# 04-POWER-P12V.net
KiCad netlist of a schematic drawn in Altium Designer
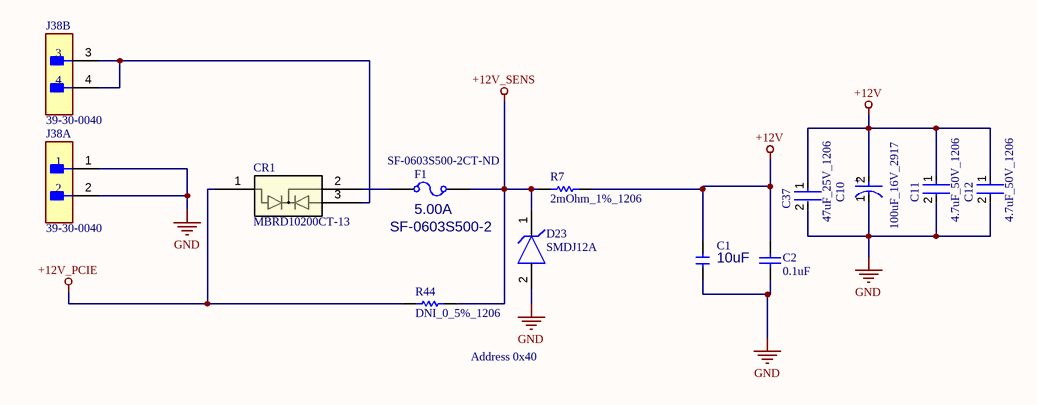
[diagram p0: 04-POWER-P12V.SchDoc]

(export (version "E")
  (design (tool "Eeschema 10.0.6"))
  (components
    (comp (ref "C1")
      (value "10uF")
      (footprint "CAPC2012X14N")
      (description "CAP, CER, 10.UF, 25V, 10%, X5R, 0805")
      (fields
        (field (name "MFG PART NUM") "TMK212BBJ106KG-T")
        (field (name "VALENTIUM PART NUM") "<VALENTIUM>")
      )
      (libsource (lib "Capacitors") (part "CAP_0805_10UF_25V"))
    )
    (comp (ref "C2")
      (value "0.1uF")
      (footprint "CAPC1608X87X45ML20T05")
      (description "C0603X104K5RACAUTO")
      (fields (field (name "MANUFACTURER") "Kemet"))
      (libsource (lib "Altium Content Vault") (part "CAP"))
    )
    (comp (ref "C10")
      (value "100uF_16V_2917")
      (footprint "FP-T495D107K016ATE125-MFG")
      (description "CAP TANT 100UF 10% 16V 2917")
      (fields (field (name "VOLTAGE") "16V") (field (name "TOLERANCE") "10%"))
      (libsource (lib "Altium Content Vault") (part "a00bbbee19879c290e62620ae7e47b1"))
    )
    (comp (ref "C11")
      (value "4.7uF_50V_1206")
      (footprint "FP-GRM31C-0_2-e0_3_0_8-IPC_C")
      (description "Chip Multilayer Ceramic Capacitors for General Purpose, 1206, 4.7uF, X7R, 15%, 10%, 50V")
      (fields (field (name "VOLTAGE") "50V") (field (name "TOLERANCE") "10%"))
      (libsource (lib "Altium Content Vault") (part "02cd4be3c70576c341d710602a673aa"))
    )
    (comp (ref "C12")
      (value "4.7uF_50V_1206")
      (footprint "FP-GRM31C-0_2-e0_3_0_8-IPC_C")
      (description "Chip Multilayer Ceramic Capacitors for General Purpose, 1206, 4.7uF, X7R, 15%, 10%, 50V")
      (fields (field (name "VOLTAGE") "50V") (field (name "TOLERANCE") "10%"))
      (libsource (lib "Altium Content Vault") (part "02cd4be3c70576c341d710602a673aa"))
    )
    (comp (ref "C37")
      (value "47uF_25V_1206")
      (footprint "FP-C3216-160-0_2-MFG")
      (description "Multilayer Ceramic Capacitors 47uF ±20% 25V X5R SMD 1206")
      (fields (field (name "VOLTAGE") "25V") (field (name "TOLERANCE") "20%"))
      (libsource (lib "Altium Content Vault") (part "11868f565c42a9108669ba33697ecf6"))
    )
    (comp (ref "CR1")
      (value "MBRD10200CT-13")
      (footprint "TO252(DPAK)_DIO")
      (description "No Description Available")
      (libsource (lib "MBRD10200CT-13") (part "MBRD10200CT-13"))
    )
    (comp (ref "D23")
      (value "SMDJ12A")
      (footprint "FP-DO-214AB_SMC_J-Bend-MFG")
      (description "TVS DIODE 12V 19.9V DO214AB")
      (libsource (lib "Altium Content Vault") (part "673ecd2ea4d7fb87b4005b0cb348b7d"))
    )
    (comp (ref "F1")
      (value "5.00A")
      (footprint "FUSM1608X60N")
      (description "FUSE SLOW 5.00A 32V M 0603")
      (fields
        (field (name "MFG PART NUM") "SF-0603S500-2")
        (field (name "VALENTIUM PART NUM") "<VALENTIUM>")
        (field (name "SUPPLIER PART NUMBER 1") "SF-0603S500-2CT-ND")
        (field (name "Comment") "FUSE_0603_5.00A")
      )
      (libsource (lib "Passives") (part "FUSE_0603_2.00A"))
    )
    (comp (ref "J38")
      (value "39-30-0040")
      (footprint "FP-39-30-0040-MFG")
      (description "CONN HEADER R/A 4POS 4.2MM")
      (fields
        (field (name "OCTOPART") "https://octopart.com/39-30-0040-molex-277428")
        (field (name "MANUFACTURER") "Molex")
      )
      (libsource (lib "Altium Content Vault") (part "ac72c5313ea981db199dbd0e8237b04"))
    )
    (comp (ref "R7")
      (value "2mOhm_1%_1206")
      (footprint "RESC3216X89X64NL25T25")
      (fields (field (name "MANUFACTURER") "Vishay Dale") (field (name "PART NUMBER") "WSL12062L000FEA18"))
      (libsource (lib "Altium Content Vault") (part "RES"))
    )
    (comp (ref "R44")
      (value "DNI_0_5%_1206")
      (footprint "RESC3116X65X50ML20T20")
      (fields (field (name "PART NUMBER") "CRCW12060000Z0EAHP") (field (name "MANUFACTURER") "Vishay Dale"))
      (libsource (lib "Altium Content Vault") (part "RES"))
    )
  )
  (nets
    (net (code "1") (name "+12V") (class "Default")
      (node (ref "C1") (pin "1") (pinfunction "1_1") (pintype "passive"))
      (node (ref "C10") (pin "2") (pinfunction "A_2") (pintype "passive"))
      (node (ref "C11") (pin "1") (pinfunction "1_1") (pintype "passive"))
      (node (ref "C12") (pin "1") (pinfunction "1_1") (pintype "passive"))
      (node (ref "C2") (pin "2") (pinfunction "2_2") (pintype "passive"))
      (node (ref "C37") (pin "1") (pinfunction "1_1") (pintype "passive"))
      (node (ref "R7") (pin "2") (pinfunction "2_2") (pintype "passive"))
    )
    (net (code "2") (name "+12V_PCIE") (class "Default")
      (node (ref "CR1") (pin "1") (pinfunction "1_1") (pintype "passive"))
      (node (ref "R44") (pin "1") (pinfunction "1_1") (pintype "passive"))
    )
    (net (code "3") (name "+12V_SENS") (class "Default")
      (node (ref "D23") (pin "1") (pinfunction "C_1") (pintype "passive"))
      (node (ref "F1") (pin "2") (pinfunction "2_2") (pintype "passive"))
      (node (ref "R44") (pin "2") (pinfunction "2_2") (pintype "passive"))
      (node (ref "R7") (pin "1") (pinfunction "1_1") (pintype "passive"))
    )
    (net (code "4") (name "GND") (class "Default")
      (node (ref "C1") (pin "2") (pinfunction "2_2") (pintype "passive"))
      (node (ref "C10") (pin "1") (pinfunction "C_1") (pintype "passive"))
      (node (ref "C11") (pin "2") (pinfunction "2_2") (pintype "passive"))
      (node (ref "C12") (pin "2") (pinfunction "2_2") (pintype "passive"))
      (node (ref "C2") (pin "1") (pinfunction "1_1") (pintype "passive"))
      (node (ref "C37") (pin "2") (pinfunction "2_2") (pintype "passive"))
      (node (ref "D23") (pin "2") (pinfunction "A_2") (pintype "passive"))
      (node (ref "J38") (pin "1") (pinfunction "1_1") (pintype "passive"))
      (node (ref "J38") (pin "2") (pinfunction "2_2") (pintype "passive"))
    )
    (net (code "5") (name "Net-(CR1-Pad2)") (class "Default")
      (node (ref "CR1") (pin "2") (pinfunction "2_2") (pintype "passive"))
      (node (ref "F1") (pin "1") (pinfunction "1_1") (pintype "passive"))
    )
    (net (code "6") (name "Net-(CR1-Pad3)") (class "Default")
      (node (ref "CR1") (pin "3") (pinfunction "3_3") (pintype "passive"))
      (node (ref "J38") (pin "3") (pinfunction "3_3") (pintype "passive"))
      (node (ref "J38") (pin "4") (pinfunction "4_4") (pintype "passive"))
    )
  )
)
